# BMS_slave_board.net
KiCad netlist of a schematic drawn in EAGLE
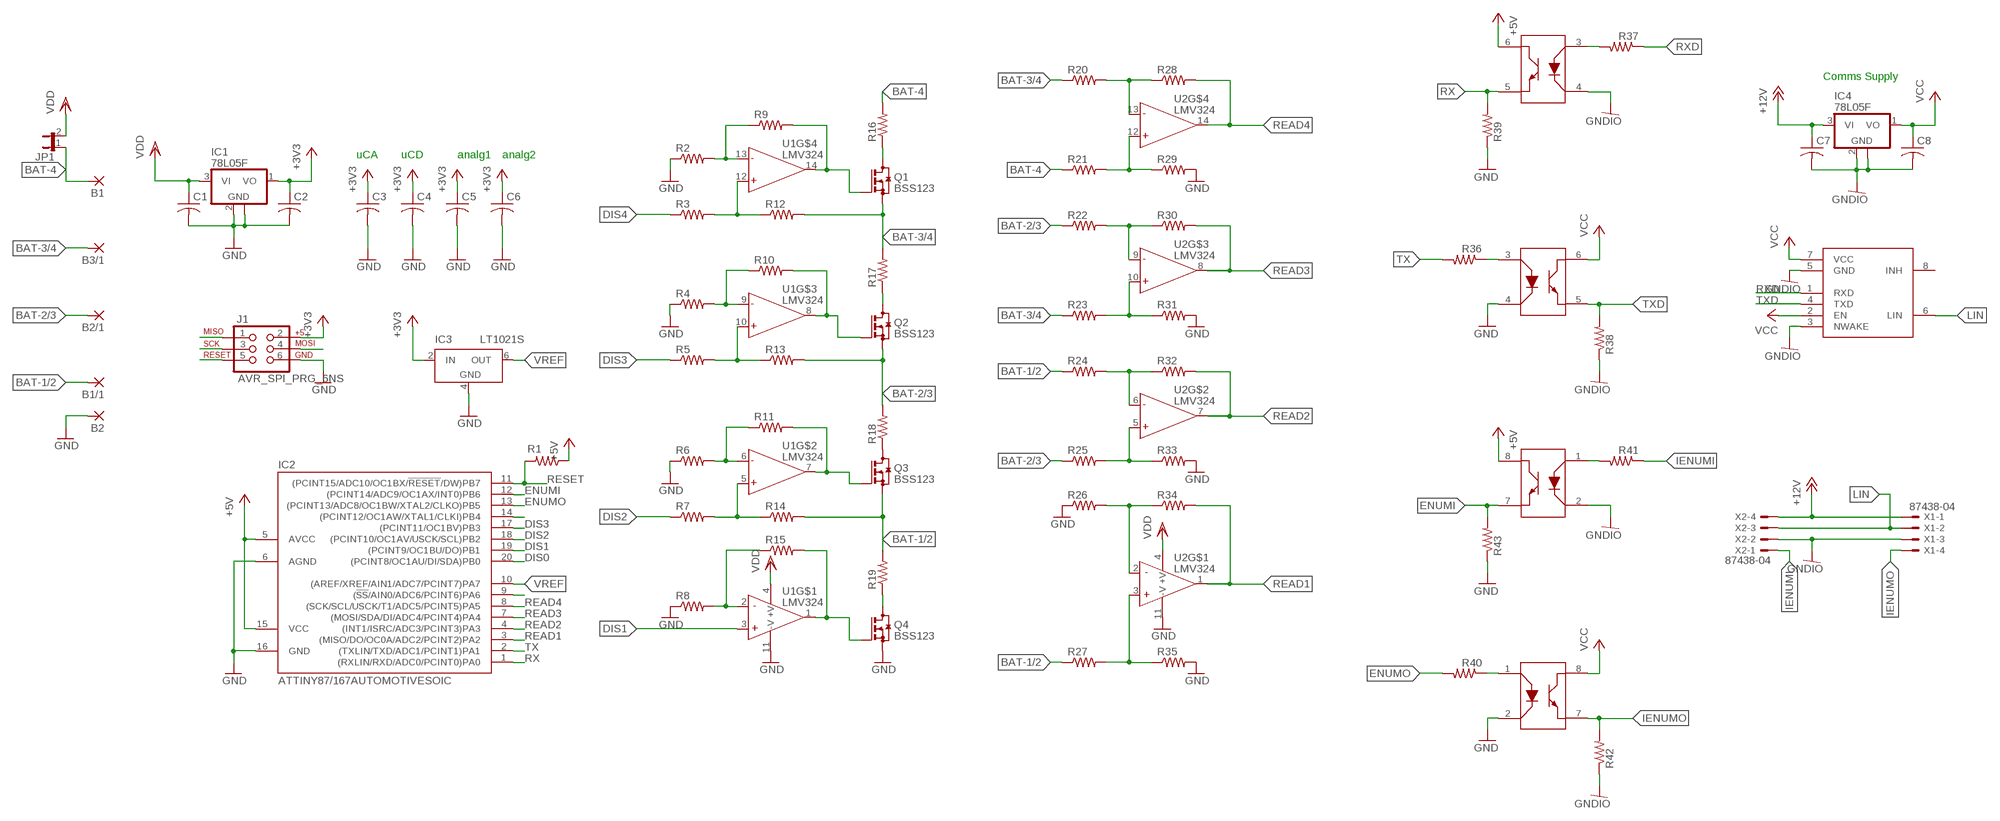
[diagram p0: schematic, sheet 1]

(export (version "E")
  (design (tool "Eeschema 10.0.6"))
  (components
    (comp (ref "B1")
      (value "2,15/1,0")
      (footprint "eagle-import:2,15_1,0")
      (libsource (lib "eagle-import") (part "2,15/1,0"))
    )
    (comp (ref "B1/1")
      (value "2,15/1,0")
      (footprint "eagle-import:2,15_1,0")
      (libsource (lib "eagle-import") (part "2,15/1,0"))
    )
    (comp (ref "B2")
      (value "2,15/1,0")
      (footprint "eagle-import:2,15_1,0")
      (libsource (lib "eagle-import") (part "2,15/1,0"))
    )
    (comp (ref "B2/1")
      (value "2,15/1,0")
      (footprint "eagle-import:2,15_1,0")
      (libsource (lib "eagle-import") (part "2,15/1,0"))
    )
    (comp (ref "B3/1")
      (value "2,15/1,0")
      (footprint "eagle-import:2,15_1,0")
      (libsource (lib "eagle-import") (part "2,15/1,0"))
    )
    (comp (ref "C1")
      (value "C-US025-024X044")
      (footprint "eagle-import:C025-024X044")
      (libsource (lib "eagle-import") (part "C-US025-024X044"))
    )
    (comp (ref "C2")
      (value "C-US025-024X044")
      (footprint "eagle-import:C025-024X044")
      (libsource (lib "eagle-import") (part "C-US025-024X044"))
    )
    (comp (ref "C3")
      (value "C-US025-024X044")
      (footprint "eagle-import:C025-024X044")
      (libsource (lib "eagle-import") (part "C-US025-024X044"))
    )
    (comp (ref "C4")
      (value "C-US025-024X044")
      (footprint "eagle-import:C025-024X044")
      (libsource (lib "eagle-import") (part "C-US025-024X044"))
    )
    (comp (ref "C5")
      (value "C-US025-024X044")
      (footprint "eagle-import:C025-024X044")
      (libsource (lib "eagle-import") (part "C-US025-024X044"))
    )
    (comp (ref "C6")
      (value "C-US025-024X044")
      (footprint "eagle-import:C025-024X044")
      (libsource (lib "eagle-import") (part "C-US025-024X044"))
    )
    (comp (ref "C7")
      (value "C-US025-024X044")
      (footprint "eagle-import:C025-024X044")
      (libsource (lib "eagle-import") (part "C-US025-024X044"))
    )
    (comp (ref "C8")
      (value "C-US025-024X044")
      (footprint "eagle-import:C025-024X044")
      (libsource (lib "eagle-import") (part "C-US025-024X044"))
    )
    (comp (ref "IC1")
      (value "78L05F")
      (footprint "eagle-import:SOT89")
      (libsource (lib "eagle-import") (part "78LF05"))
    )
    (comp (ref "IC2")
      (value "ATTINY87/167AUTOMOTIVESOIC")
      (footprint "eagle-import:SO20L")
      (libsource (lib "eagle-import") (part "ATTINY87/167AUTOMOTIVESOIC"))
    )
    (comp (ref "IC3")
      (value "LT1021S")
      (footprint "eagle-import:SOIC8")
      (fields (field (name "MPN") "LT1021DCS8-10#PBF"))
      (libsource (lib "eagle-import") (part "LT1021S"))
    )
    (comp (ref "IC4")
      (value "78L05F")
      (footprint "eagle-import:SOT89")
      (libsource (lib "eagle-import") (part "78LF05"))
    )
    (comp (ref "J1")
      (value "AVR_SPI_PRG_6NS")
      (footprint "eagle-import:2X3-NS")
      (libsource (lib "eagle-import") (part "AVR_SPI_PRG_6NS"))
    )
    (comp (ref "JP1")
      (value "JP1E")
      (footprint "eagle-import:JP1")
      (libsource (lib "eagle-import") (part "JP1E"))
    )
    (comp (ref "Q1")
      (value "BSS123")
      (footprint "eagle-import:SOT23")
      (libsource (lib "eagle-import") (part "BSS123"))
    )
    (comp (ref "Q2")
      (value "BSS123")
      (footprint "eagle-import:SOT23")
      (libsource (lib "eagle-import") (part "BSS123"))
    )
    (comp (ref "Q3")
      (value "BSS123")
      (footprint "eagle-import:SOT23")
      (libsource (lib "eagle-import") (part "BSS123"))
    )
    (comp (ref "Q4")
      (value "BSS123")
      (footprint "eagle-import:SOT23")
      (libsource (lib "eagle-import") (part "BSS123"))
    )
    (comp (ref "R1")
      (value "R-US_R0603")
      (footprint "eagle-import:R0603")
      (libsource (lib "eagle-import") (part "R-US_R0603"))
    )
    (comp (ref "R2")
      (value "R-US_R0603")
      (footprint "eagle-import:R0603")
      (libsource (lib "eagle-import") (part "R-US_R0603"))
    )
    (comp (ref "R3")
      (value "R-US_R0603")
      (footprint "eagle-import:R0603")
      (libsource (lib "eagle-import") (part "R-US_R0603"))
    )
    (comp (ref "R4")
      (value "R-US_R0603")
      (footprint "eagle-import:R0603")
      (libsource (lib "eagle-import") (part "R-US_R0603"))
    )
    (comp (ref "R5")
      (value "R-US_R0603")
      (footprint "eagle-import:R0603")
      (libsource (lib "eagle-import") (part "R-US_R0603"))
    )
    (comp (ref "R6")
      (value "R-US_R0603")
      (footprint "eagle-import:R0603")
      (libsource (lib "eagle-import") (part "R-US_R0603"))
    )
    (comp (ref "R7")
      (value "R-US_R0603")
      (footprint "eagle-import:R0603")
      (libsource (lib "eagle-import") (part "R-US_R0603"))
    )
    (comp (ref "R8")
      (value "R-US_R0603")
      (footprint "eagle-import:R0603")
      (libsource (lib "eagle-import") (part "R-US_R0603"))
    )
    (comp (ref "R9")
      (value "R-US_R0603")
      (footprint "eagle-import:R0603")
      (libsource (lib "eagle-import") (part "R-US_R0603"))
    )
    (comp (ref "R10")
      (value "R-US_R0603")
      (footprint "eagle-import:R0603")
      (libsource (lib "eagle-import") (part "R-US_R0603"))
    )
    (comp (ref "R11")
      (value "R-US_R0603")
      (footprint "eagle-import:R0603")
      (libsource (lib "eagle-import") (part "R-US_R0603"))
    )
    (comp (ref "R12")
      (value "R-US_R0603")
      (footprint "eagle-import:R0603")
      (libsource (lib "eagle-import") (part "R-US_R0603"))
    )
    (comp (ref "R13")
      (value "R-US_R0603")
      (footprint "eagle-import:R0603")
      (libsource (lib "eagle-import") (part "R-US_R0603"))
    )
    (comp (ref "R14")
      (value "R-US_R0603")
      (footprint "eagle-import:R0603")
      (libsource (lib "eagle-import") (part "R-US_R0603"))
    )
    (comp (ref "R15")
      (value "R-US_R0603")
      (footprint "eagle-import:R0603")
      (libsource (lib "eagle-import") (part "R-US_R0603"))
    )
    (comp (ref "R16")
      (value "R-US_R0603")
      (footprint "eagle-import:R0603")
      (libsource (lib "eagle-import") (part "R-US_R0603"))
    )
    (comp (ref "R17")
      (value "R-US_R0603")
      (footprint "eagle-import:R0603")
      (libsource (lib "eagle-import") (part "R-US_R0603"))
    )
    (comp (ref "R18")
      (value "R-US_R0603")
      (footprint "eagle-import:R0603")
      (libsource (lib "eagle-import") (part "R-US_R0603"))
    )
    (comp (ref "R19")
      (value "R-US_R0603")
      (footprint "eagle-import:R0603")
      (libsource (lib "eagle-import") (part "R-US_R0603"))
    )
    (comp (ref "R20")
      (value "R-US_M0805")
      (footprint "eagle-import:M0805")
      (libsource (lib "eagle-import") (part "R-US_M0805"))
    )
    (comp (ref "R21")
      (value "R-US_R0603")
      (footprint "eagle-import:R0603")
      (libsource (lib "eagle-import") (part "R-US_R0603"))
    )
    (comp (ref "R22")
      (value "R-US_R0603")
      (footprint "eagle-import:R0603")
      (libsource (lib "eagle-import") (part "R-US_R0603"))
    )
    (comp (ref "R23")
      (value "R-US_R0603")
      (footprint "eagle-import:R0603")
      (libsource (lib "eagle-import") (part "R-US_R0603"))
    )
    (comp (ref "R24")
      (value "R-US_R0603")
      (footprint "eagle-import:R0603")
      (libsource (lib "eagle-import") (part "R-US_R0603"))
    )
    (comp (ref "R25")
      (value "R-US_R0603")
      (footprint "eagle-import:R0603")
      (libsource (lib "eagle-import") (part "R-US_R0603"))
    )
    (comp (ref "R26")
      (value "R-US_R0603")
      (footprint "eagle-import:R0603")
      (libsource (lib "eagle-import") (part "R-US_R0603"))
    )
    (comp (ref "R27")
      (value "R-US_R0603")
      (footprint "eagle-import:R0603")
      (libsource (lib "eagle-import") (part "R-US_R0603"))
    )
    (comp (ref "R28")
      (value "R-US_R0603")
      (footprint "eagle-import:R0603")
      (libsource (lib "eagle-import") (part "R-US_R0603"))
    )
    (comp (ref "R29")
      (value "R-US_R0603")
      (footprint "eagle-import:R0603")
      (libsource (lib "eagle-import") (part "R-US_R0603"))
    )
    (comp (ref "R30")
      (value "R-US_R0603")
      (footprint "eagle-import:R0603")
      (libsource (lib "eagle-import") (part "R-US_R0603"))
    )
    (comp (ref "R31")
      (value "R-US_R0603")
      (footprint "eagle-import:R0603")
      (libsource (lib "eagle-import") (part "R-US_R0603"))
    )
    (comp (ref "R32")
      (value "R-US_R0603")
      (footprint "eagle-import:R0603")
      (libsource (lib "eagle-import") (part "R-US_R0603"))
    )
    (comp (ref "R33")
      (value "R-US_R0603")
      (footprint "eagle-import:R0603")
      (libsource (lib "eagle-import") (part "R-US_R0603"))
    )
    (comp (ref "R34")
      (value "R-US_R0603")
      (footprint "eagle-import:R0603")
      (libsource (lib "eagle-import") (part "R-US_R0603"))
    )
    (comp (ref "R35")
      (value "R-US_R0603")
      (footprint "eagle-import:R0603")
      (libsource (lib "eagle-import") (part "R-US_R0603"))
    )
    (comp (ref "R36")
      (value "R-US_R0603")
      (footprint "eagle-import:R0603")
      (libsource (lib "eagle-import") (part "R-US_R0603"))
    )
    (comp (ref "R37")
      (value "R-US_R0603")
      (footprint "eagle-import:R0603")
      (libsource (lib "eagle-import") (part "R-US_R0603"))
    )
    (comp (ref "R38")
      (value "R-US_R0603")
      (footprint "eagle-import:R0603")
      (libsource (lib "eagle-import") (part "R-US_R0603"))
    )
    (comp (ref "R39")
      (value "R-US_R0603")
      (footprint "eagle-import:R0603")
      (libsource (lib "eagle-import") (part "R-US_R0603"))
    )
    (comp (ref "R40")
      (value "R-US_R0603")
      (footprint "eagle-import:R0603")
      (libsource (lib "eagle-import") (part "R-US_R0603"))
    )
    (comp (ref "R41")
      (value "R-US_R0603")
      (footprint "eagle-import:R0603")
      (libsource (lib "eagle-import") (part "R-US_R0603"))
    )
    (comp (ref "R42")
      (value "R-US_R0603")
      (footprint "eagle-import:R0603")
      (libsource (lib "eagle-import") (part "R-US_R0603"))
    )
    (comp (ref "R43")
      (value "R-US_R0603")
      (footprint "eagle-import:R0603")
      (libsource (lib "eagle-import") (part "R-US_R0603"))
    )
    (comp (ref "U$1")
      (value "LTV-827SMD")
      (footprint "eagle-import:SO08")
      (libsource (lib "eagle-import") (part "LTV-827SMD"))
    )
    (comp (ref "U$2")
      (value "LTV-827SMD")
      (footprint "eagle-import:SO08")
      (libsource (lib "eagle-import") (part "LTV-827SMD"))
    )
    (comp (ref "U$3")
      (value "TPIC1021")
      (footprint "eagle-import:SO08")
      (libsource (lib "eagle-import") (part "TPIC1021"))
    )
    (comp (ref "U1")
      (value "LMV324")
      (footprint "eagle-import:SO014")
      (libsource (lib "eagle-import") (part "LMV324"))
    )
    (comp (ref "U2")
      (value "LMV324")
      (footprint "eagle-import:SO014")
      (libsource (lib "eagle-import") (part "LMV324"))
    )
    (comp (ref "X1")
      (value "87438-04")
      (footprint "eagle-import:87438-04")
      (libsource (lib "eagle-import") (part "87438-04"))
    )
    (comp (ref "X2")
      (value "87438-04")
      (footprint "eagle-import:87438-04")
      (libsource (lib "eagle-import") (part "87438-04"))
    )
  )
  (nets
    (net (code "1") (name "+3V3") (class "Default")
      (node (ref "C2") (pin "1") (pinfunction "1_1") (pintype "passive"))
      (node (ref "C3") (pin "1") (pinfunction "1_1") (pintype "passive"))
      (node (ref "C4") (pin "1") (pinfunction "1_1") (pintype "passive"))
      (node (ref "C5") (pin "1") (pinfunction "1_1") (pintype "passive"))
      (node (ref "C6") (pin "1") (pinfunction "1_1") (pintype "passive"))
      (node (ref "IC1") (pin "1") (pinfunction "VO_1") (pintype "passive"))
      (node (ref "IC3") (pin "2") (pinfunction "IN_2") (pintype "input"))
      (node (ref "J1") (pin "2") (pinfunction "2_2") (pintype "passive"))
    )
    (net (code "2") (name "+5V") (class "Default")
      (node (ref "IC2") (pin "15") (pinfunction "VCC_15") (pintype "power_in"))
      (node (ref "IC2") (pin "5") (pinfunction "AVCC_5") (pintype "bidirectional"))
      (node (ref "R1") (pin "1") (pinfunction "1_1") (pintype "passive"))
      (node (ref "U$2") (pin "6") (pinfunction "CO_6") (pintype "bidirectional"))
      (node (ref "U$2") (pin "8") (pinfunction "CO_8") (pintype "bidirectional"))
    )
    (net (code "3") (name "+12V") (class "Default")
      (node (ref "C7") (pin "1") (pinfunction "1_1") (pintype "passive"))
      (node (ref "IC4") (pin "3") (pinfunction "VI_3") (pintype "input"))
      (node (ref "X1") (pin "1") (pinfunction "S_1") (pintype "passive"))
      (node (ref "X2") (pin "4") (pinfunction "S_4") (pintype "passive"))
    )
    (net (code "4") (name "/DIS0") (class "Default")
      (node (ref "IC2") (pin "20") (pinfunction "(PCINT8/OC1AU/DI/SDA)PB0_20") (pintype "bidirectional"))
    )
    (net (code "5") (name "/RESET") (class "Default")
      (node (ref "IC2") (pin "11") (pinfunction "(PCINT15/ADC10/OC1BX/~{RESET}/DW)PB7_11") (pintype "bidirectional"))
      (node (ref "J1") (pin "5") (pinfunction "5_5") (pintype "passive"))
      (node (ref "R1") (pin "2") (pinfunction "2_2") (pintype "passive"))
    )
    (net (code "6") (name "BAT-1{slash}2") (class "Default")
      (node (ref "B1/1") (pin "1") (pinfunction "P_1") (pintype "passive"))
      (node (ref "Q3") (pin "2") (pinfunction "S_2") (pintype "passive"))
      (node (ref "R14") (pin "2") (pinfunction "2_2") (pintype "passive"))
      (node (ref "R19") (pin "2") (pinfunction "2_2") (pintype "passive"))
      (node (ref "R24") (pin "1") (pinfunction "1_1") (pintype "passive"))
      (node (ref "R27") (pin "1") (pinfunction "1_1") (pintype "passive"))
    )
    (net (code "7") (name "BAT-2{slash}3") (class "Default")
      (node (ref "B2/1") (pin "1") (pinfunction "P_1") (pintype "passive"))
      (node (ref "Q2") (pin "2") (pinfunction "S_2") (pintype "passive"))
      (node (ref "R13") (pin "2") (pinfunction "2_2") (pintype "passive"))
      (node (ref "R18") (pin "2") (pinfunction "2_2") (pintype "passive"))
      (node (ref "R22") (pin "1") (pinfunction "1_1") (pintype "passive"))
      (node (ref "R25") (pin "1") (pinfunction "1_1") (pintype "passive"))
    )
    (net (code "8") (name "BAT-3{slash}4") (class "Default")
      (node (ref "B3/1") (pin "1") (pinfunction "P_1") (pintype "passive"))
      (node (ref "Q1") (pin "2") (pinfunction "S_2") (pintype "passive"))
      (node (ref "R12") (pin "2") (pinfunction "2_2") (pintype "passive"))
      (node (ref "R17") (pin "2") (pinfunction "2_2") (pintype "passive"))
      (node (ref "R20") (pin "1") (pinfunction "1_1") (pintype "passive"))
      (node (ref "R23") (pin "1") (pinfunction "1_1") (pintype "passive"))
    )
    (net (code "9") (name "BAT-4") (class "Default")
      (node (ref "B1") (pin "1") (pinfunction "P_1") (pintype "passive"))
      (node (ref "JP1") (pin "1") (pinfunction "1_1") (pintype "passive"))
      (node (ref "R16") (pin "2") (pinfunction "2_2") (pintype "passive"))
      (node (ref "R21") (pin "1") (pinfunction "1_1") (pintype "passive"))
    )
    (net (code "10") (name "DIS1") (class "Default")
      (node (ref "IC2") (pin "19") (pinfunction "(PCINT9/OC1BU/DO)PB1_19") (pintype "bidirectional"))
      (node (ref "U1") (pin "3") (pinfunction "+IN_3") (pintype "input"))
    )
    (net (code "11") (name "DIS2") (class "Default")
      (node (ref "IC2") (pin "18") (pinfunction "(PCINT10/OC1AV/USCK/SCL)PB2_18") (pintype "bidirectional"))
      (node (ref "R7") (pin "1") (pinfunction "1_1") (pintype "passive"))
    )
    (net (code "12") (name "DIS3") (class "Default")
      (node (ref "IC2") (pin "17") (pinfunction "(PCINT11/OC1BV)PB3_17") (pintype "bidirectional"))
      (node (ref "R5") (pin "1") (pinfunction "1_1") (pintype "passive"))
    )
    (net (code "13") (name "DIS4") (class "Default")
      (node (ref "R3") (pin "1") (pinfunction "1_1") (pintype "passive"))
    )
    (net (code "14") (name "ENUMI") (class "Default")
      (node (ref "IC2") (pin "12") (pinfunction "(PCINT14/ADC9/OC1AX/INT0)PB6_12") (pintype "bidirectional"))
      (node (ref "R43") (pin "2") (pinfunction "2_2") (pintype "passive"))
      (node (ref "U$2") (pin "7") (pinfunction "E_7") (pintype "bidirectional"))
    )
    (net (code "15") (name "ENUMO") (class "Default")
      (node (ref "IC2") (pin "13") (pinfunction "(PCINT13/ADC8/OC1BW/XTAL2/CLKO)PB5_13") (pintype "bidirectional"))
      (node (ref "R40") (pin "2") (pinfunction "2_2") (pintype "passive"))
    )
    (net (code "16") (name "GND") (class "Default")
      (node (ref "B2") (pin "1") (pinfunction "P_1") (pintype "passive"))
      (node (ref "C1") (pin "2") (pinfunction "2_2") (pintype "passive"))
      (node (ref "C2") (pin "2") (pinfunction "2_2") (pintype "passive"))
      (node (ref "C3") (pin "2") (pinfunction "2_2") (pintype "passive"))
      (node (ref "C4") (pin "2") (pinfunction "2_2") (pintype "passive"))
      (node (ref "C5") (pin "2") (pinfunction "2_2") (pintype "passive"))
      (node (ref "C6") (pin "2") (pinfunction "2_2") (pintype "passive"))
      (node (ref "IC1") (pin "2") (pinfunction "GND_2") (pintype "passive"))
      (node (ref "IC1") (pin "2@1") (pinfunction "GND_2@1") (pintype "passive"))
      (node (ref "IC2") (pin "16") (pinfunction "GND_16") (pintype "power_in"))
      (node (ref "IC2") (pin "6") (pinfunction "AGND_6") (pintype "bidirectional"))
      (node (ref "IC3") (pin "4") (pinfunction "GND_4") (pintype "power_in"))
      (node (ref "J1") (pin "6") (pinfunction "6_6") (pintype "passive"))
      (node (ref "Q4") (pin "2") (pinfunction "S_2") (pintype "passive"))
      (node (ref "R2") (pin "1") (pinfunction "1_1") (pintype "passive"))
      (node (ref "R26") (pin "1") (pinfunction "1_1") (pintype "passive"))
      (node (ref "R29") (pin "2") (pinfunction "2_2") (pintype "passive"))
      (node (ref "R31") (pin "2") (pinfunction "2_2") (pintype "passive"))
      (node (ref "R33") (pin "2") (pinfunction "2_2") (pintype "passive"))
      (node (ref "R35") (pin "2") (pinfunction "2_2") (pintype "passive"))
      (node (ref "R39") (pin "1") (pinfunction "1_1") (pintype "passive"))
      (node (ref "R4") (pin "1") (pinfunction "1_1") (pintype "passive"))
      (node (ref "R43") (pin "1") (pinfunction "1_1") (pintype "passive"))
      (node (ref "R6") (pin "1") (pinfunction "1_1") (pintype "passive"))
      (node (ref "R8") (pin "1") (pinfunction "1_1") (pintype "passive"))
      (node (ref "U$1") (pin "2") (pinfunction "CA_2") (pintype "bidirectional"))
      (node (ref "U$1") (pin "4") (pinfunction "CA_4") (pintype "bidirectional"))
      (node (ref "U1") (pin "11") (pinfunction "-V_11") (pintype "power_in"))
      (node (ref "U2") (pin "11") (pinfunction "-V_11") (pintype "power_in"))
    )
    (net (code "17") (name "GNDIO") (class "Default")
      (node (ref "C7") (pin "2") (pinfunction "2_2") (pintype "passive"))
      (node (ref "C8") (pin "2") (pinfunction "2_2") (pintype "passive"))
      (node (ref "IC4") (pin "2") (pinfunction "GND_2") (pintype "passive"))
      (node (ref "IC4") (pin "2@1") (pinfunction "GND_2@1") (pintype "passive"))
      (node (ref "R38") (pin "1") (pinfunction "1_1") (pintype "passive"))
      (node (ref "R42") (pin "1") (pinfunction "1_1") (pintype "passive"))
      (node (ref "U$2") (pin "2") (pinfunction "CA_2") (pintype "bidirectional"))
      (node (ref "U$2") (pin "4") (pinfunction "CA_4") (pintype "bidirectional"))
      (node (ref "U$3") (pin "3") (pinfunction "NWAKE_3") (pintype "input"))
      (node (ref "U$3") (pin "5") (pinfunction "GND_5") (pintype "power_in"))
      (node (ref "X1") (pin "3") (pinfunction "S_3") (pintype "passive"))
      (node (ref "X2") (pin "2") (pinfunction "S_2") (pintype "passive"))
    )
    (net (code "18") (name "IENUMI") (class "Default")
      (node (ref "R41") (pin "1") (pinfunction "1_1") (pintype "passive"))
      (node (ref "X2") (pin "1") (pinfunction "S_1") (pintype "passive"))
    )
    (net (code "19") (name "IENUMO") (class "Default")
      (node (ref "R42") (pin "2") (pinfunction "2_2") (pintype "passive"))
      (node (ref "U$1") (pin "7") (pinfunction "E_7") (pintype "bidirectional"))
      (node (ref "X1") (pin "4") (pinfunction "S_4") (pintype "passive"))
    )
    (net (code "20") (name "LIN") (class "Default")
      (node (ref "U$3") (pin "6") (pinfunction "LIN_6") (pintype "bidirectional"))
      (node (ref "X1") (pin "2") (pinfunction "S_2") (pintype "passive"))
      (node (ref "X2") (pin "3") (pinfunction "S_3") (pintype "passive"))
    )
    (net (code "21") (name "Net-(Q1-D)") (class "Default")
      (node (ref "Q1") (pin "3") (pinfunction "D_3") (pintype "passive"))
      (node (ref "R16") (pin "1") (pinfunction "1_1") (pintype "passive"))
    )
    (net (code "22") (name "Net-(Q1-G)") (class "Default")
      (node (ref "Q1") (pin "1") (pinfunction "G_1") (pintype "passive"))
      (node (ref "R9") (pin "2") (pinfunction "2_2") (pintype "passive"))
      (node (ref "U1") (pin "14") (pinfunction "OUT_14") (pintype "power_in"))
    )
    (net (code "23") (name "Net-(Q2-D)") (class "Default")
      (node (ref "Q2") (pin "3") (pinfunction "D_3") (pintype "passive"))
      (node (ref "R17") (pin "1") (pinfunction "1_1") (pintype "passive"))
    )
    (net (code "24") (name "Net-(Q2-G)") (class "Default")
      (node (ref "Q2") (pin "1") (pinfunction "G_1") (pintype "passive"))
      (node (ref "R10") (pin "2") (pinfunction "2_2") (pintype "passive"))
      (node (ref "U1") (pin "8") (pinfunction "OUT_8") (pintype "power_in"))
    )
    (net (code "25") (name "Net-(Q3-D)") (class "Default")
      (node (ref "Q3") (pin "3") (pinfunction "D_3") (pintype "passive"))
      (node (ref "R18") (pin "1") (pinfunction "1_1") (pintype "passive"))
    )
    (net (code "26") (name "Net-(Q3-G)") (class "Default")
      (node (ref "Q3") (pin "1") (pinfunction "G_1") (pintype "passive"))
      (node (ref "R11") (pin "2") (pinfunction "2_2") (pintype "passive"))
      (node (ref "U1") (pin "7") (pinfunction "OUT_7") (pintype "power_in"))
    )
    (net (code "27") (name "Net-(Q4-D)") (class "Default")
      (node (ref "Q4") (pin "3") (pinfunction "D_3") (pintype "passive"))
      (node (ref "R19") (pin "1") (pinfunction "1_1") (pintype "passive"))
    )
    (net (code "28") (name "Net-(Q4-G)") (class "Default")
      (node (ref "Q4") (pin "1") (pinfunction "G_1") (pintype "passive"))
      (node (ref "R15") (pin "2") (pinfunction "2_2") (pintype "passive"))
      (node (ref "U1") (pin "1") (pinfunction "OUT_1") (pintype "output"))
    )
    (net (code "29") (name "Net-(U$1A-A)") (class "Default")
      (node (ref "R40") (pin "1") (pinfunction "1_1") (pintype "passive"))
      (node (ref "U$1") (pin "1") (pinfunction "A_1") (pintype "bidirectional"))
    )
    (net (code "30") (name "Net-(U$1B-A)") (class "Default")
      (node (ref "R36") (pin "1") (pinfunction "1_1") (pintype "passive"))
      (node (ref "U$1") (pin "3") (pinfunction "A_3") (pintype "bidirectional"))
    )
    (net (code "31") (name "Net-(U$2A-A)") (class "Default")
      (node (ref "R41") (pin "2") (pinfunction "2_2") (pintype "passive"))
      (node (ref "U$2") (pin "1") (pinfunction "A_1") (pintype "bidirectional"))
    )
    (net (code "32") (name "Net-(U$2B-A)") (class "Default")
      (node (ref "R37") (pin "2") (pinfunction "2_2") (pintype "passive"))
      (node (ref "U$2") (pin "3") (pinfunction "A_3") (pintype "bidirectional"))
    )
    (net (code "33") (name "Net-(U1A--IN)") (class "Default")
      (node (ref "R15") (pin "1") (pinfunction "1_1") (pintype "passive"))
      (node (ref "R8") (pin "2") (pinfunction "2_2") (pintype "passive"))
      (node (ref "U1") (pin "2") (pinfunction "-IN_2") (pintype "input"))
    )
    (net (code "34") (name "Net-(U1B-+IN)") (class "Default")
      (node (ref "R14") (pin "1") (pinfunction "1_1") (pintype "passive"))
      (node (ref "R7") (pin "2") (pinfunction "2_2") (pintype "passive"))
      (node (ref "U1") (pin "5") (pinfunction "+IN_5") (pintype "power_in"))
    )
    (net (code "35") (name "Net-(U1B--IN)") (class "Default")
      (node (ref "R11") (pin "1") (pinfunction "1_1") (pintype "passive"))
      (node (ref "R6") (pin "2") (pinfunction "2_2") (pintype "passive"))
      (node (ref "U1") (pin "6") (pinfunction "-IN_6") (pintype "power_in"))
    )
    (net (code "36") (name "Net-(U1C-+IN)") (class "Default")
      (node (ref "R13") (pin "1") (pinfunction "1_1") (pintype "passive"))
      (node (ref "R5") (pin "2") (pinfunction "2_2") (pintype "passive"))
      (node (ref "U1") (pin "10") (pinfunction "+IN_10") (pintype "power_in"))
    )
    (net (code "37") (name "Net-(U1C--IN)") (class "Default")
      (node (ref "R10") (pin "1") (pinfunction "1_1") (pintype "passive"))
      (node (ref "R4") (pin "2") (pinfunction "2_2") (pintype "passive"))
      (node (ref "U1") (pin "9") (pinfunction "-IN_9") (pintype "power_in"))
    )
    (net (code "38") (name "Net-(U1D-+IN)") (class "Default")
      (node (ref "R12") (pin "1") (pinfunction "1_1") (pintype "passive"))
      (node (ref "R3") (pin "2") (pinfunction "2_2") (pintype "passive"))
      (node (ref "U1") (pin "12") (pinfunction "+IN_12") (pintype "power_in"))
    )
    (net (code "39") (name "Net-(U1D--IN)") (class "Default")
      (node (ref "R2") (pin "2") (pinfunction "2_2") (pintype "passive"))
      (node (ref "R9") (pin "1") (pinfunction "1_1") (pintype "passive"))
      (node (ref "U1") (pin "13") (pinfunction "-IN_13") (pintype "power_in"))
    )
    (net (code "40") (name "Net-(U2A-+IN)") (class "Default")
      (node (ref "R27") (pin "2") (pinfunction "2_2") (pintype "passive"))
      (node (ref "R35") (pin "1") (pinfunction "1_1") (pintype "passive"))
      (node (ref "U2") (pin "3") (pinfunction "+IN_3") (pintype "input"))
    )
    (net (code "41") (name "Net-(U2A--IN)") (class "Default")
      (node (ref "R26") (pin "2") (pinfunction "2_2") (pintype "passive"))
      (node (ref "R34") (pin "1") (pinfunction "1_1") (pintype "passive"))
      (node (ref "U2") (pin "2") (pinfunction "-IN_2") (pintype "input"))
    )
    (net (code "42") (name "Net-(U2B-+IN)") (class "Default")
      (node (ref "R25") (pin "2") (pinfunction "2_2") (pintype "passive"))
      (node (ref "R33") (pin "1") (pinfunction "1_1") (pintype "passive"))
      (node (ref "U2") (pin "5") (pinfunction "+IN_5") (pintype "power_in"))
    )
    (net (code "43") (name "Net-(U2B--IN)") (class "Default")
      (node (ref "R24") (pin "2") (pinfunction "2_2") (pintype "passive"))
      (node (ref "R32") (pin "1") (pinfunction "1_1") (pintype "passive"))
      (node (ref "U2") (pin "6") (pinfunction "-IN_6") (pintype "power_in"))
    )
    (net (code "44") (name "Net-(U2C-+IN)") (class "Default")
      (node (ref "R23") (pin "2") (pinfunction "2_2") (pintype "passive"))
      (node (ref "R31") (pin "1") (pinfunction "1_1") (pintype "passive"))
      (node (ref "U2") (pin "10") (pinfunction "+IN_10") (pintype "power_in"))
    )
    (net (code "45") (name "Net-(U2C--IN)") (class "Default")
      (node (ref "R22") (pin "2") (pinfunction "2_2") (pintype "passive"))
      (node (ref "R30") (pin "1") (pinfunction "1_1") (pintype "passive"))
      (node (ref "U2") (pin "9") (pinfunction "-IN_9") (pintype "power_in"))
    )
    (net (code "46") (name "Net-(U2D-+IN)") (class "Default")
      (node (ref "R21") (pin "2") (pinfunction "2_2") (pintype "passive"))
      (node (ref "R29") (pin "1") (pinfunction "1_1") (pintype "passive"))
      (node (ref "U2") (pin "12") (pinfunction "+IN_12") (pintype "power_in"))
    )
    (net (code "47") (name "Net-(U2D--IN)") (class "Default")
      (node (ref "R20") (pin "2") (pinfunction "2_2") (pintype "passive"))
      (node (ref "R28") (pin "1") (pinfunction "1_1") (pintype "passive"))
      (node (ref "U2") (pin "13") (pinfunction "-IN_13") (pintype "power_in"))
    )
    (net (code "48") (name "READ1") (class "Default")
      (node (ref "IC2") (pin "3") (pinfunction "(MISO/DO/OC0A/ADC2/PCINT2)PA2_3") (pintype "bidirectional"))
      (node (ref "J1") (pin "1") (pinfunction "1_1") (pintype "passive"))
      (node (ref "R34") (pin "2") (pinfunction "2_2") (pintype "passive"))
      (node (ref "U2") (pin "1") (pinfunction "OUT_1") (pintype "output"))
    )
    (net (code "49") (name "READ2") (class "Default")
      (node (ref "IC2") (pin "4") (pinfunction "(INT1/ISRC/ADC3/PCINT3)PA3_4") (pintype "bidirectional"))
      (node (ref "R32") (pin "2") (pinfunction "2_2") (pintype "passive"))
      (node (ref "U2") (pin "7") (pinfunction "OUT_7") (pintype "power_in"))
    )
    (net (code "50") (name "READ3") (class "Default")
      (node (ref "IC2") (pin "7") (pinfunction "(MOSI/SDA/DI/ADC4/PCINT4)PA4_7") (pintype "bidirectional"))
      (node (ref "J1") (pin "4") (pinfunction "4_4") (pintype "passive"))
      (node (ref "R30") (pin "2") (pinfunction "2_2") (pintype "passive"))
      (node (ref "U2") (pin "8") (pinfunction "OUT_8") (pintype "power_in"))
    )
    (net (code "51") (name "READ4") (class "Default")
      (node (ref "IC2") (pin "8") (pinfunction "(SCK/SCL/USCK/T1/ADC5/PCINT5)PA5_8") (pintype "bidirectional"))
      (node (ref "J1") (pin "3") (pinfunction "3_3") (pintype "passive"))
      (node (ref "R28") (pin "2") (pinfunction "2_2") (pintype "passive"))
      (node (ref "U2") (pin "14") (pinfunction "OUT_14") (pintype "power_in"))
    )
    (net (code "52") (name "RX") (class "Default")
      (node (ref "IC2") (pin "1") (pinfunction "(RXLIN/RXD/ADC0/PCINT0)PA0_1") (pintype "bidirectional"))
      (node (ref "R39") (pin "2") (pinfunction "2_2") (pintype "passive"))
      (node (ref "U$2") (pin "5") (pinfunction "E_5") (pintype "bidirectional"))
    )
    (net (code "53") (name "RXD") (class "Default")
      (node (ref "R37") (pin "1") (pinfunction "1_1") (pintype "passive"))
      (node (ref "U$3") (pin "1") (pinfunction "RXD_1") (pintype "output"))
    )
    (net (code "54") (name "TX") (class "Default")
      (node (ref "IC2") (pin "2") (pinfunction "(TXLIN/TXD/ADC1/PCINT1)PA1_2") (pintype "bidirectional"))
      (node (ref "R36") (pin "2") (pinfunction "2_2") (pintype "passive"))
    )
    (net (code "55") (name "TXD") (class "Default")
      (node (ref "R38") (pin "2") (pinfunction "2_2") (pintype "passive"))
      (node (ref "U$1") (pin "5") (pinfunction "E_5") (pintype "bidirectional"))
      (node (ref "U$3") (pin "4") (pinfunction "TXD_4") (pintype "bidirectional"))
    )
    (net (code "56") (name "VCC") (class "Default")
      (node (ref "C8") (pin "1") (pinfunction "1_1") (pintype "passive"))
      (node (ref "IC4") (pin "1") (pinfunction "VO_1") (pintype "passive"))
      (node (ref "U$1") (pin "6") (pinfunction "CO_6") (pintype "bidirectional"))
      (node (ref "U$1") (pin "8") (pinfunction "CO_8") (pintype "bidirectional"))
      (node (ref "U$3") (pin "2") (pinfunction "EN_2") (pintype "input"))
      (node (ref "U$3") (pin "7") (pinfunction "VCC_7") (pintype "power_in"))
    )
    (net (code "57") (name "VDD") (class "Default")
      (node (ref "C1") (pin "1") (pinfunction "1_1") (pintype "passive"))
      (node (ref "IC1") (pin "3") (pinfunction "VI_3") (pintype "input"))
      (node (ref "JP1") (pin "2") (pinfunction "2_2") (pintype "passive"))
      (node (ref "U1") (pin "4") (pinfunction "+V_4") (pintype "power_in"))
      (node (ref "U2") (pin "4") (pinfunction "+V_4") (pintype "power_in"))
    )
    (net (code "58") (name "VREF") (class "Default")
      (node (ref "IC2") (pin "10") (pinfunction "(AREF/XREF/AIN1/ADC7/PCINT7)PA7_10") (pintype "bidirectional"))
      (node (ref "IC3") (pin "6") (pinfunction "OUT_6") (pintype "output"))
    )
    (net (code "59") (name "unconnected-(IC2-(PCINT12{slash}OC1AW{slash}XTAL1{slash}CLKI)PB4-Pad14)") (class "Default")
      (node (ref "IC2") (pin "14") (pinfunction "(PCINT12/OC1AW/XTAL1/CLKI)PB4_14") (pintype "bidirectional"))
    )
    (net (code "60") (name "unconnected-(IC2-(~{SS}{slash}AIN0{slash}ADC6{slash}PCINT6)PA6-Pad9)") (class "Default")
      (node (ref "IC2") (pin "9") (pinfunction "(~{SS}/AIN0/ADC6/PCINT6)PA6_9") (pintype "bidirectional"))
    )
    (net (code "61") (name "unconnected-(U$3-INH-Pad8)") (class "Default")
      (node (ref "U$3") (pin "8") (pinfunction "INH_8") (pintype "output"))
    )
  )
)
